# Woodenmachine.net
KiCad netlist of a schematic drawn in EAGLE
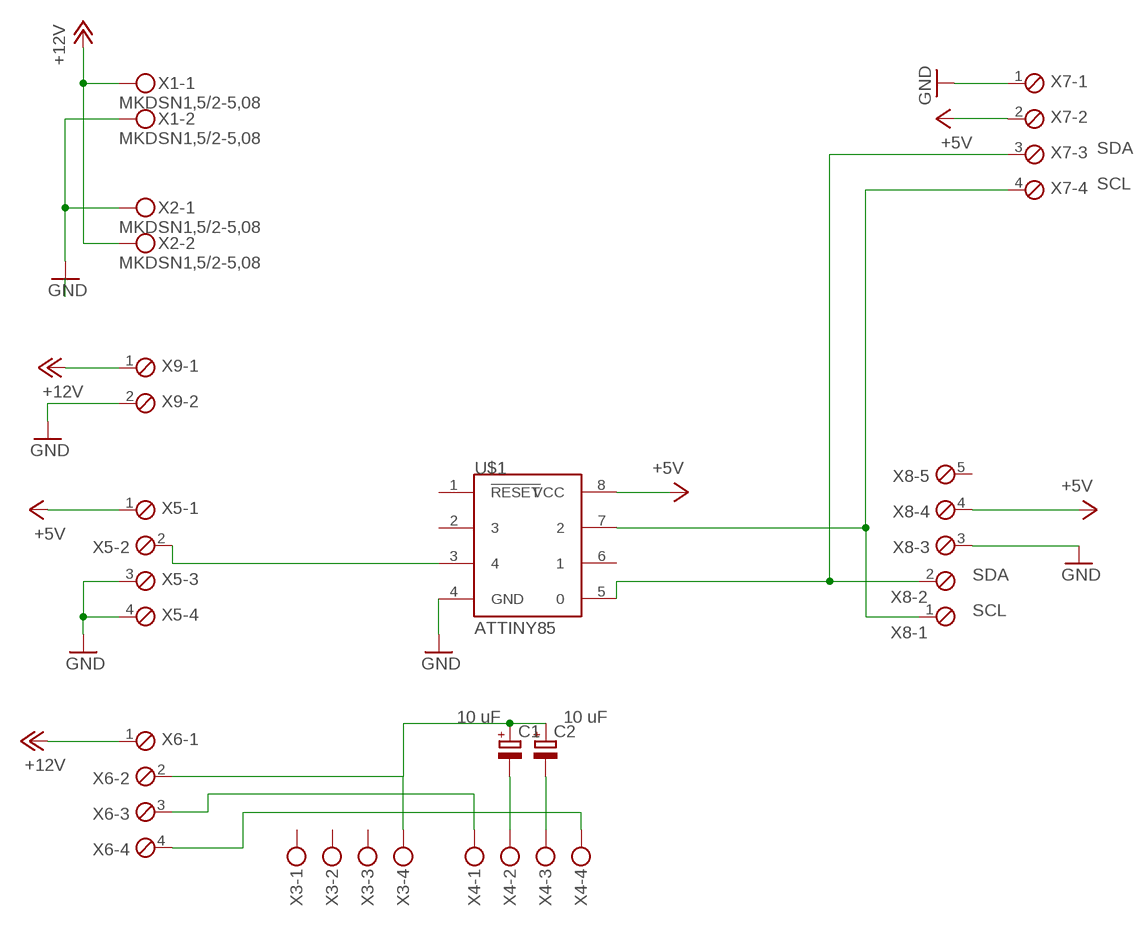
[diagram p0: schematic, sheet 1]

(export (version "E")
  (design (tool "Eeschema 10.0.6"))
  (components
    (comp (ref "C1")
      (value "CPOL-EUE2.5-5")
      (footprint "eagle-import:E2,5-5")
      (fields (field (name "CAP") "10 uF"))
      (libsource (lib "eagle-import") (part "CPOL-EUE2.5-5"))
    )
    (comp (ref "C2")
      (value "CPOL-EUE2.5-5")
      (footprint "eagle-import:E2,5-5")
      (fields (field (name "CAP") "10 uF"))
      (libsource (lib "eagle-import") (part "CPOL-EUE2.5-5"))
    )
    (comp (ref "U$1")
      (value "ATTINY85")
      (footprint "eagle-import:8P3")
      (libsource (lib "eagle-import") (part "ATTINY85"))
    )
    (comp (ref "X1")
      (value "MKDSN1,5/2-5,08")
      (footprint "eagle-import:MKDSN1,5_2-5,08")
      (libsource (lib "eagle-import") (part "MKDSN1,5/2-5,08"))
    )
    (comp (ref "X2")
      (value "MKDSN1,5/2-5,08")
      (footprint "eagle-import:MKDSN1,5_2-5,08")
      (libsource (lib "eagle-import") (part "MKDSN1,5/2-5,08"))
    )
    (comp (ref "X3")
      (value "MKDSN1,5/4-5,08")
      (footprint "eagle-import:MKDSN1,5_4-5,08")
      (libsource (lib "eagle-import") (part "MKDSN1,5/4-5,08"))
    )
    (comp (ref "X4")
      (value "MKDSN1,5/4-5,08")
      (footprint "eagle-import:MKDSN1,5_4-5,08")
      (libsource (lib "eagle-import") (part "MKDSN1,5/4-5,08"))
    )
    (comp (ref "X5")
      (value "MPT4")
      (footprint "eagle-import:4POL254")
      (libsource (lib "eagle-import") (part "MPT4"))
    )
    (comp (ref "X6")
      (value "MPT4")
      (footprint "eagle-import:4POL254")
      (libsource (lib "eagle-import") (part "MPT4"))
    )
    (comp (ref "X7")
      (value "MPT4")
      (footprint "eagle-import:4POL254")
      (fields (field (name "SCL") "SCL") (field (name "SDA") "SDA"))
      (libsource (lib "eagle-import") (part "MPT4"))
    )
    (comp (ref "X8")
      (value "MPT5")
      (footprint "eagle-import:5POL254")
      (fields (field (name "SCL") "SCL") (field (name "SDA") "SDA"))
      (libsource (lib "eagle-import") (part "MPT5"))
    )
    (comp (ref "X9")
      (value "MPT2")
      (footprint "eagle-import:2POL254")
      (libsource (lib "eagle-import") (part "MPT2"))
    )
  )
  (nets
    (net (code "1") (name "+5V") (class "Default")
      (node (ref "U$1") (pin "8") (pinfunction "VCC_8") (pintype "power_in"))
      (node (ref "X5") (pin "1") (pinfunction "1_1") (pintype "passive"))
      (node (ref "X7") (pin "2") (pinfunction "1_2") (pintype "passive"))
      (node (ref "X8") (pin "4") (pinfunction "1_4") (pintype "passive"))
    )
    (net (code "2") (name "+12V") (class "Default")
      (node (ref "X1") (pin "1") (pinfunction "KL_1") (pintype "passive"))
      (node (ref "X2") (pin "2") (pinfunction "KL_2") (pintype "passive"))
      (node (ref "X6") (pin "1") (pinfunction "1_1") (pintype "passive"))
      (node (ref "X9") (pin "1") (pinfunction "1_1") (pintype "passive"))
    )
    (net (code "3") (name "GND") (class "Default")
      (node (ref "U$1") (pin "4") (pinfunction "GND_4") (pintype "power_in"))
      (node (ref "X1") (pin "2") (pinfunction "KL_2") (pintype "passive"))
      (node (ref "X2") (pin "1") (pinfunction "KL_1") (pintype "passive"))
      (node (ref "X5") (pin "3") (pinfunction "1_3") (pintype "passive"))
      (node (ref "X5") (pin "4") (pinfunction "1_4") (pintype "passive"))
      (node (ref "X7") (pin "1") (pinfunction "1_1") (pintype "passive"))
      (node (ref "X8") (pin "3") (pinfunction "1_3") (pintype "passive"))
      (node (ref "X9") (pin "2") (pinfunction "1_2") (pintype "passive"))
    )
    (net (code "4") (name "Net-(U$1-0)") (class "Default")
      (node (ref "U$1") (pin "5") (pinfunction "0_5") (pintype "bidirectional"))
      (node (ref "X7") (pin "3") (pinfunction "1_3") (pintype "passive"))
      (node (ref "X8") (pin "2") (pinfunction "1_2") (pintype "passive"))
    )
    (net (code "5") (name "Net-(U$1-2)") (class "Default")
      (node (ref "U$1") (pin "7") (pinfunction "2_7") (pintype "bidirectional"))
      (node (ref "X7") (pin "4") (pinfunction "1_4") (pintype "passive"))
      (node (ref "X8") (pin "1") (pinfunction "1_1") (pintype "passive"))
    )
    (net (code "6") (name "Net-(U$1-4)") (class "Default")
      (node (ref "U$1") (pin "3") (pinfunction "4_3") (pintype "bidirectional"))
      (node (ref "X5") (pin "2") (pinfunction "1_2") (pintype "passive"))
    )
    (net (code "7") (name "Net-(X3D-KL)") (class "Default")
      (node (ref "C1") (pin "+") (pinfunction "+_+") (pintype "passive"))
      (node (ref "C2") (pin "+") (pinfunction "+_+") (pintype "passive"))
      (node (ref "X3") (pin "4") (pinfunction "KL_4") (pintype "passive"))
      (node (ref "X6") (pin "2") (pinfunction "1_2") (pintype "passive"))
    )
    (net (code "8") (name "Net-(X4A-KL)") (class "Default")
      (node (ref "X4") (pin "1") (pinfunction "KL_1") (pintype "passive"))
      (node (ref "X6") (pin "3") (pinfunction "1_3") (pintype "passive"))
    )
    (net (code "9") (name "Net-(X4B-KL)") (class "Default")
      (node (ref "C1") (pin "-") (pinfunction "-_-") (pintype "passive"))
      (node (ref "X4") (pin "2") (pinfunction "KL_2") (pintype "passive"))
    )
    (net (code "10") (name "Net-(X4C-KL)") (class "Default")
      (node (ref "C2") (pin "-") (pinfunction "-_-") (pintype "passive"))
      (node (ref "X4") (pin "3") (pinfunction "KL_3") (pintype "passive"))
    )
    (net (code "11") (name "Net-(X4D-KL)") (class "Default")
      (node (ref "X4") (pin "4") (pinfunction "KL_4") (pintype "passive"))
      (node (ref "X6") (pin "4") (pinfunction "1_4") (pintype "passive"))
    )
    (net (code "12") (name "unconnected-(U$1-1-Pad6)") (class "Default")
      (node (ref "U$1") (pin "6") (pinfunction "1_6") (pintype "bidirectional"))
    )
    (net (code "13") (name "unconnected-(U$1-3-Pad2)") (class "Default")
      (node (ref "U$1") (pin "2") (pinfunction "3_2") (pintype "bidirectional"))
    )
    (net (code "14") (name "unconnected-(U$1-~{RESET}-Pad1)") (class "Default")
      (node (ref "U$1") (pin "1") (pinfunction "~{RESET}_1") (pintype "bidirectional"))
    )
    (net (code "15") (name "unconnected-(X3A-KL-Pad1)") (class "Default")
      (node (ref "X3") (pin "1") (pinfunction "KL_1") (pintype "passive"))
    )
    (net (code "16") (name "unconnected-(X3B-KL-Pad2)") (class "Default")
      (node (ref "X3") (pin "2") (pinfunction "KL_2") (pintype "passive"))
    )
    (net (code "17") (name "unconnected-(X3C-KL-Pad3)") (class "Default")
      (node (ref "X3") (pin "3") (pinfunction "KL_3") (pintype "passive"))
    )
    (net (code "18") (name "unconnected-(X8E-1-Pad5)") (class "Default")
      (node (ref "X8") (pin "5") (pinfunction "1_5") (pintype "passive"))
    )
  )
)
